# ATMEGA-BOARD.net
KiCad netlist of a schematic drawn in Altium Designer
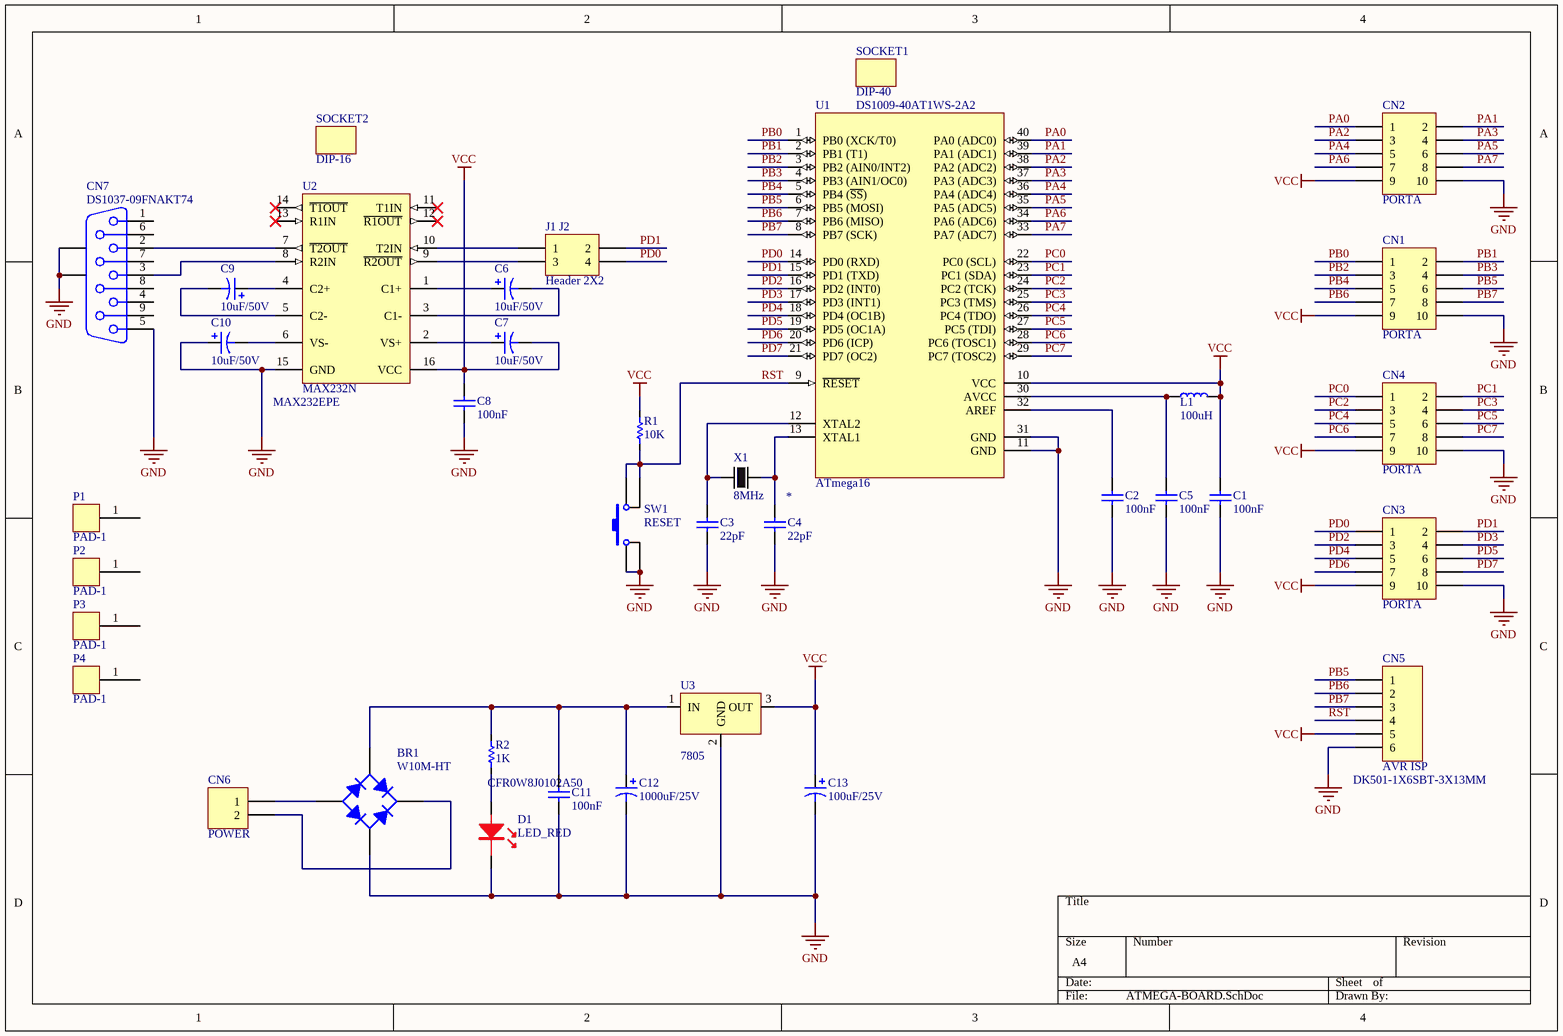
[diagram p0: ATMEGA-BOARD.SchDoc]

(export (version "E")
  (design (tool "Eeschema 10.0.6"))
  (components
    (comp (ref "BR1")
      (value "W10M-HT")
      (footprint "DIODE-WOB")
      (description "Full Wave Diode Bridge")
      (libsource (lib "Miscellaneous Devices") (part "Bridge1"))
    )
    (comp (ref "C1")
      (value "100nF")
      (footprint "CAP0.2N")
      (description "Capacitor")
      (libsource (lib "Miscellaneous Devices") (part "Cap"))
    )
    (comp (ref "C2")
      (value "100nF")
      (footprint "CAP0.2N")
      (description "Capacitor")
      (libsource (lib "Miscellaneous Devices") (part "Cap"))
    )
    (comp (ref "C3")
      (value "22pF")
      (footprint "CAP0.2N")
      (description "Capacitor")
      (libsource (lib "Miscellaneous Devices") (part "Cap"))
    )
    (comp (ref "C4")
      (value "22pF")
      (footprint "CAP0.2N")
      (description "Capacitor")
      (libsource (lib "Miscellaneous Devices") (part "Cap"))
    )
    (comp (ref "C5")
      (value "100nF")
      (footprint "CAP0.2N")
      (description "Capacitor")
      (libsource (lib "Miscellaneous Devices") (part "Cap"))
    )
    (comp (ref "C6")
      (value "10uF/50V")
      (footprint "CAP_ALUM_5x11x2.5_V")
      (description "Polarized Capacitor")
      (libsource (lib "Miscellaneous Devices") (part "Cap Pol3"))
    )
    (comp (ref "C7")
      (value "10uF/50V")
      (footprint "CAP_ALUM_5x11x2.5_V")
      (description "Polarized Capacitor")
      (libsource (lib "Miscellaneous Devices") (part "Cap Pol3"))
    )
    (comp (ref "C8")
      (value "100nF")
      (footprint "CAP0.2N")
      (description "Capacitor")
      (libsource (lib "Miscellaneous Devices") (part "Cap"))
    )
    (comp (ref "C9")
      (value "10uF/50V")
      (footprint "CAP_ALUM_5x11x2.5_V")
      (description "Polarized Capacitor")
      (libsource (lib "Miscellaneous Devices") (part "Cap Pol3"))
    )
    (comp (ref "C10")
      (value "10uF/50V")
      (footprint "CAP_ALUM_5x11x2.5_V")
      (description "Polarized Capacitor")
      (libsource (lib "Miscellaneous Devices") (part "Cap Pol3"))
    )
    (comp (ref "C11")
      (value "100nF")
      (footprint "CAP0.2N")
      (description "Capacitor")
      (libsource (lib "Miscellaneous Devices") (part "Cap"))
    )
    (comp (ref "C12")
      (value "1000uF/25V")
      (footprint "CAP_ALUM_10x17x5_V")
      (description "Polarized Capacitor")
      (libsource (lib "Miscellaneous Devices") (part "Cap Pol3"))
    )
    (comp (ref "C13")
      (value "100uF/25V")
      (footprint "CAP_ALUM_6.3x11.2x2.5_V")
      (description "Polarized Capacitor")
      (libsource (lib "Miscellaneous Devices") (part "Cap Pol3"))
    )
    (comp (ref "CN1")
      (value "PORTA")
      (footprint "CON-DS1013-10SSIB1")
      (description "Header, 5-Pin, Dual row, Right Angle")
      (libsource (lib "Miscellaneous Connectors") (part "Header 5X2H"))
    )
    (comp (ref "CN2")
      (value "PORTA")
      (footprint "CON-DS1013-10SSIB1")
      (description "Header, 5-Pin, Dual row, Right Angle")
      (libsource (lib "Miscellaneous Connectors") (part "Header 5X2H"))
    )
    (comp (ref "CN3")
      (value "PORTA")
      (footprint "CON-DS1013-10SSIB1")
      (description "Header, 5-Pin, Dual row, Right Angle")
      (libsource (lib "Miscellaneous Connectors") (part "Header 5X2H"))
    )
    (comp (ref "CN4")
      (value "PORTA")
      (footprint "CON-DS1013-10SSIB1")
      (description "Header, 5-Pin, Dual row, Right Angle")
      (libsource (lib "Miscellaneous Connectors") (part "Header 5X2H"))
    )
    (comp (ref "CN5")
      (value "AVR ISP")
      (footprint "Pin Header S/M 06x1 TH Pitch 2.54mm")
      (description "Header, 6-Pin")
      (fields (field (name "OZDISAN KODU") "DK501-1X6SBT-3X13MM"))
      (libsource (lib "Miscellaneous Connectors") (part "Header 6"))
    )
    (comp (ref "CN6")
      (value "POWER")
      (footprint "Klemens-DG126-5.0-02P-14-00AH")
      (description "Header, 2-Pin")
      (libsource (lib "Miscellaneous Connectors") (part "Header 2"))
    )
    (comp (ref "CN7")
      (value "DS1037-09FNAKT74")
      (footprint "CON-DB9FLW")
      (description "CONNECTOR DSUB 9PIN 90C PCB TYPE FEMALE")
      (libsource (lib "Miscellaneous Connectors") (part "D Connector 9"))
    )
    (comp (ref "D1") (value "LED_RED") (footprint "LED3M-RED") (libsource (lib "ali_lib") (part "LED_RED")))
    (comp (ref "J1 J2")
      (value "Header 2X2")
      (footprint "Pin Header S/M 02x2 TH Pitch 2.54mm")
      (description "Header, 2-Pin, Dual row")
      (libsource (lib "Miscellaneous Connectors") (part "Header 2X2"))
    )
    (comp (ref "L1")
      (value "100uH")
      (footprint "IND-AL0412")
      (description "Inductor")
      (libsource (lib "ali_lib") (part "Inductor"))
    )
    (comp (ref "P1") (value "PAD-1") (footprint "DOUBLE-3") (libsource (lib "ali_lib") (part "PAD-1")))
    (comp (ref "P2") (value "PAD-1") (footprint "DOUBLE-3") (libsource (lib "ali_lib") (part "PAD-1")))
    (comp (ref "P3") (value "PAD-1") (footprint "DOUBLE-3") (libsource (lib "ali_lib") (part "PAD-1")))
    (comp (ref "P4") (value "PAD-1") (footprint "DOUBLE-3") (libsource (lib "ali_lib") (part "PAD-1")))
    (comp (ref "R1")
      (value "10K")
      (footprint "RES_AXIAL-0.3")
      (description "Resistor")
      (libsource (lib "ali_lib") (part "R"))
    )
    (comp (ref "R2")
      (value "1K")
      (footprint "RES_AXIAL-0.3")
      (description "Resistor")
      (fields (field (name "OZDISAN KODU") "CFR0W8J0102A50"))
      (libsource (lib "ali_lib") (part "R"))
    )
    (comp (ref "SOCKET1")
      (value "DIP-40")
      (fields (field (name "OZDISAN KODU") "DS1009-40AT1WS-2A2"))
      (libsource (lib "ali_lib") (part "MECHANIC"))
    )
    (comp (ref "SOCKET2") (value "DIP-16") (libsource (lib "ali_lib") (part "MECHANIC")))
    (comp (ref "SW1")
      (value "RESET")
      (footprint "Switch-6x6x4.3")
      (description "Switch")
      (libsource (lib "ali_lib") (part "SW-PB"))
    )
    (comp (ref "U1")
      (value "ATmega16")
      (footprint "DIP40N")
      (description "8-bit AVR Microcontroller, 4.5-5.5V")
      (fields (field (name "OZDISAN KODU") "*"))
      (libsource (lib "ali_lib") (part "MC-8B-ATM32-IL40"))
    )
    (comp (ref "U2")
      (value "MAX232N")
      (footprint "DIP16N")
      (description "Dual EIA-232 Driver / Receiver, 0 to 70 degC, 16-Pin PDIP (N), Pb-Free (RoHS)")
      (fields (field (name "OZDISAN KODU") "MAX232EPE"))
      (libsource (lib "ali_lib") (part "TI-MAX232-PDIP_N-16"))
    )
    (comp (ref "U3")
      (value "7805")
      (footprint "TO-220_3-H")
      (description "IC REG LINEAR 5V 500MA DPAK")
      (libsource (lib "ali_lib") (part "78M05"))
    )
    (comp (ref "X1")
      (value "8MHz")
      (footprint "XTAL_DIP")
      (description "XTAL")
      (libsource (lib "ali_lib") (part "XTAL"))
    )
  )
  (nets
    (net (code "1") (name "/PA0") (class "Default")
      (node (ref "CN2") (pin "1") (pinfunction "1_1") (pintype "passive"))
      (node (ref "U1") (pin "40") (pinfunction "PA0_(ADC0)_40") (pintype "bidirectional"))
    )
    (net (code "2") (name "/PA1") (class "Default")
      (node (ref "CN2") (pin "2") (pinfunction "2_2") (pintype "passive"))
      (node (ref "U1") (pin "39") (pinfunction "PA1_(ADC1)_39") (pintype "bidirectional"))
    )
    (net (code "3") (name "/PA2") (class "Default")
      (node (ref "CN2") (pin "3") (pinfunction "3_3") (pintype "passive"))
      (node (ref "U1") (pin "38") (pinfunction "PA2_(ADC2)_38") (pintype "bidirectional"))
    )
    (net (code "4") (name "/PA3") (class "Default")
      (node (ref "CN2") (pin "4") (pinfunction "4_4") (pintype "passive"))
      (node (ref "U1") (pin "37") (pinfunction "PA3_(ADC3)_37") (pintype "bidirectional"))
    )
    (net (code "5") (name "/PA4") (class "Default")
      (node (ref "CN2") (pin "5") (pinfunction "5_5") (pintype "passive"))
      (node (ref "U1") (pin "36") (pinfunction "PA4_(ADC4)_36") (pintype "bidirectional"))
    )
    (net (code "6") (name "/PA5") (class "Default")
      (node (ref "CN2") (pin "6") (pinfunction "6_6") (pintype "passive"))
      (node (ref "U1") (pin "35") (pinfunction "PA5_(ADC5)_35") (pintype "bidirectional"))
    )
    (net (code "7") (name "/PA6") (class "Default")
      (node (ref "CN2") (pin "7") (pinfunction "7_7") (pintype "passive"))
      (node (ref "U1") (pin "34") (pinfunction "PA6_(ADC6)_34") (pintype "bidirectional"))
    )
    (net (code "8") (name "/PA7") (class "Default")
      (node (ref "CN2") (pin "8") (pinfunction "8_8") (pintype "passive"))
      (node (ref "U1") (pin "33") (pinfunction "PA7_(ADC7)_33") (pintype "bidirectional"))
    )
    (net (code "9") (name "/PB0") (class "Default")
      (node (ref "CN1") (pin "1") (pinfunction "1_1") (pintype "passive"))
      (node (ref "U1") (pin "1") (pinfunction "PB0_(XCK/T0)_1") (pintype "bidirectional"))
    )
    (net (code "10") (name "/PB1") (class "Default")
      (node (ref "CN1") (pin "2") (pinfunction "2_2") (pintype "passive"))
      (node (ref "U1") (pin "2") (pinfunction "PB1_(T1)_2") (pintype "bidirectional"))
    )
    (net (code "11") (name "/PB2") (class "Default")
      (node (ref "CN1") (pin "3") (pinfunction "3_3") (pintype "passive"))
      (node (ref "U1") (pin "3") (pinfunction "PB2_(AIN0/INT2)_3") (pintype "bidirectional"))
    )
    (net (code "12") (name "/PB3") (class "Default")
      (node (ref "CN1") (pin "4") (pinfunction "4_4") (pintype "passive"))
      (node (ref "U1") (pin "4") (pinfunction "PB3_(AIN1/OC0)_4") (pintype "bidirectional"))
    )
    (net (code "13") (name "/PB4") (class "Default")
      (node (ref "CN1") (pin "5") (pinfunction "5_5") (pintype "passive"))
      (node (ref "U1") (pin "5") (pinfunction "PB4_(~{SS})_5") (pintype "bidirectional"))
    )
    (net (code "14") (name "/PB5") (class "Default")
      (node (ref "CN1") (pin "6") (pinfunction "6_6") (pintype "passive"))
      (node (ref "CN5") (pin "1") (pinfunction "1_1") (pintype "passive"))
      (node (ref "U1") (pin "6") (pinfunction "PB5_(MOSI)_6") (pintype "bidirectional"))
    )
    (net (code "15") (name "/PB6") (class "Default")
      (node (ref "CN1") (pin "7") (pinfunction "7_7") (pintype "passive"))
      (node (ref "CN5") (pin "2") (pinfunction "2_2") (pintype "passive"))
      (node (ref "U1") (pin "7") (pinfunction "PB6_(MISO)_7") (pintype "bidirectional"))
    )
    (net (code "16") (name "/PB7") (class "Default")
      (node (ref "CN1") (pin "8") (pinfunction "8_8") (pintype "passive"))
      (node (ref "CN5") (pin "3") (pinfunction "3_3") (pintype "passive"))
      (node (ref "U1") (pin "8") (pinfunction "PB7_(SCK)_8") (pintype "bidirectional"))
    )
    (net (code "17") (name "/PC0") (class "Default")
      (node (ref "CN4") (pin "1") (pinfunction "1_1") (pintype "passive"))
      (node (ref "U1") (pin "22") (pinfunction "PC0_(SCL)_22") (pintype "bidirectional"))
    )
    (net (code "18") (name "/PC1") (class "Default")
      (node (ref "CN4") (pin "2") (pinfunction "2_2") (pintype "passive"))
      (node (ref "U1") (pin "23") (pinfunction "PC1_(SDA)_23") (pintype "bidirectional"))
    )
    (net (code "19") (name "/PC2") (class "Default")
      (node (ref "CN4") (pin "3") (pinfunction "3_3") (pintype "passive"))
      (node (ref "U1") (pin "24") (pinfunction "PC2_(TCK)_24") (pintype "bidirectional"))
    )
    (net (code "20") (name "/PC3") (class "Default")
      (node (ref "CN4") (pin "4") (pinfunction "4_4") (pintype "passive"))
      (node (ref "U1") (pin "25") (pinfunction "PC3_(TMS)_25") (pintype "bidirectional"))
    )
    (net (code "21") (name "/PC4") (class "Default")
      (node (ref "CN4") (pin "5") (pinfunction "5_5") (pintype "passive"))
      (node (ref "U1") (pin "26") (pinfunction "PC4_(TDO)_26") (pintype "bidirectional"))
    )
    (net (code "22") (name "/PC5") (class "Default")
      (node (ref "CN4") (pin "6") (pinfunction "6_6") (pintype "passive"))
      (node (ref "U1") (pin "27") (pinfunction "PC5_(TDI)_27") (pintype "bidirectional"))
    )
    (net (code "23") (name "/PC6") (class "Default")
      (node (ref "CN4") (pin "7") (pinfunction "7_7") (pintype "passive"))
      (node (ref "U1") (pin "28") (pinfunction "PC6_(TOSC1)_28") (pintype "bidirectional"))
    )
    (net (code "24") (name "/PC7") (class "Default")
      (node (ref "CN4") (pin "8") (pinfunction "8_8") (pintype "passive"))
      (node (ref "U1") (pin "29") (pinfunction "PC7_(TOSC2)_29") (pintype "bidirectional"))
    )
    (net (code "25") (name "/PD0") (class "Default")
      (node (ref "CN3") (pin "1") (pinfunction "1_1") (pintype "passive"))
      (node (ref "J1 J2") (pin "4") (pinfunction "4_4") (pintype "passive"))
      (node (ref "U1") (pin "14") (pinfunction "PD0_(RXD)_14") (pintype "bidirectional"))
    )
    (net (code "26") (name "/PD1") (class "Default")
      (node (ref "CN3") (pin "2") (pinfunction "2_2") (pintype "passive"))
      (node (ref "J1 J2") (pin "2") (pinfunction "2_2") (pintype "passive"))
      (node (ref "U1") (pin "15") (pinfunction "PD1_(TXD)_15") (pintype "bidirectional"))
    )
    (net (code "27") (name "/PD2") (class "Default")
      (node (ref "CN3") (pin "3") (pinfunction "3_3") (pintype "passive"))
      (node (ref "U1") (pin "16") (pinfunction "PD2_(INT0)_16") (pintype "bidirectional"))
    )
    (net (code "28") (name "/PD3") (class "Default")
      (node (ref "CN3") (pin "4") (pinfunction "4_4") (pintype "passive"))
      (node (ref "U1") (pin "17") (pinfunction "PD3_(INT1)_17") (pintype "bidirectional"))
    )
    (net (code "29") (name "/PD4") (class "Default")
      (node (ref "CN3") (pin "5") (pinfunction "5_5") (pintype "passive"))
      (node (ref "U1") (pin "18") (pinfunction "PD4_(OC1B)_18") (pintype "bidirectional"))
    )
    (net (code "30") (name "/PD5") (class "Default")
      (node (ref "CN3") (pin "6") (pinfunction "6_6") (pintype "passive"))
      (node (ref "U1") (pin "19") (pinfunction "PD5_(OC1A)_19") (pintype "bidirectional"))
    )
    (net (code "31") (name "/PD6") (class "Default")
      (node (ref "CN3") (pin "7") (pinfunction "7_7") (pintype "passive"))
      (node (ref "U1") (pin "20") (pinfunction "PD6_(ICP)_20") (pintype "bidirectional"))
    )
    (net (code "32") (name "/PD7") (class "Default")
      (node (ref "CN3") (pin "8") (pinfunction "8_8") (pintype "passive"))
      (node (ref "U1") (pin "21") (pinfunction "PD7_(OC2)_21") (pintype "bidirectional"))
    )
    (net (code "33") (name "/RST") (class "Default")
      (node (ref "CN5") (pin "4") (pinfunction "4_4") (pintype "passive"))
      (node (ref "R1") (pin "1") (pinfunction "1_1") (pintype "passive"))
      (node (ref "SW1") (pin "2") (pinfunction "2_2") (pintype "passive"))
      (node (ref "U1") (pin "9") (pinfunction "~{RESET}_9") (pintype "input"))
    )
    (net (code "34") (name "GND") (class "Default")
      (node (ref "BR1") (pin "2") (pinfunction "C_2") (pintype "passive"))
      (node (ref "C1") (pin "1") (pinfunction "1_1") (pintype "passive"))
      (node (ref "C10") (pin "1") (pinfunction "1_1") (pintype "passive"))
      (node (ref "C11") (pin "1") (pinfunction "1_1") (pintype "passive"))
      (node (ref "C12") (pin "2") (pinfunction "2_2") (pintype "passive"))
      (node (ref "C13") (pin "2") (pinfunction "2_2") (pintype "passive"))
      (node (ref "C2") (pin "1") (pinfunction "1_1") (pintype "passive"))
      (node (ref "C3") (pin "1") (pinfunction "1_1") (pintype "passive"))
      (node (ref "C4") (pin "1") (pinfunction "1_1") (pintype "passive"))
      (node (ref "C5") (pin "1") (pinfunction "1_1") (pintype "passive"))
      (node (ref "C8") (pin "1") (pinfunction "1_1") (pintype "passive"))
      (node (ref "CN1") (pin "10") (pinfunction "10_10") (pintype "passive"))
      (node (ref "CN2") (pin "10") (pinfunction "10_10") (pintype "passive"))
      (node (ref "CN3") (pin "10") (pinfunction "10_10") (pintype "passive"))
      (node (ref "CN4") (pin "10") (pinfunction "10_10") (pintype "passive"))
      (node (ref "CN5") (pin "6") (pinfunction "6_6") (pintype "passive"))
      (node (ref "CN7") (pin "5") (pinfunction "5_5") (pintype "passive"))
      (node (ref "CN7") (pin "BO1") (pinfunction "MH2_BO1") (pintype "passive"))
      (node (ref "CN7") (pin "BO2") (pinfunction "MH1_BO2") (pintype "passive"))
      (node (ref "D1") (pin "2") (pinfunction "K_2") (pintype "passive"))
      (node (ref "SW1") (pin "1") (pinfunction "1_1") (pintype "passive"))
      (node (ref "U1") (pin "11") (pinfunction "GND_11") (pintype "power_in"))
      (node (ref "U1") (pin "31") (pinfunction "GND_31") (pintype "power_in"))
      (node (ref "U2") (pin "15") (pinfunction "GND_15") (pintype "power_in"))
      (node (ref "U3") (pin "2") (pinfunction "GND_2") (pintype "passive"))
    )
    (net (code "35") (name "Net-(BR1-A)") (class "Default")
      (node (ref "BR1") (pin "3") (pinfunction "A_3") (pintype "passive"))
      (node (ref "CN6") (pin "1") (pinfunction "1_1") (pintype "passive"))
    )
    (net (code "36") (name "Net-(BR1-K)") (class "Default")
      (node (ref "BR1") (pin "1") (pinfunction "K_1") (pintype "passive"))
      (node (ref "CN6") (pin "2") (pinfunction "2_2") (pintype "passive"))
    )
    (net (code "37") (name "Net-(D1-A)") (class "Default")
      (node (ref "D1") (pin "1") (pinfunction "A_1") (pintype "passive"))
      (node (ref "R2") (pin "1") (pinfunction "1_1") (pintype "passive"))
    )
    (net (code "38") (name "Net-(U1-AREF)") (class "Default")
      (node (ref "C2") (pin "2") (pinfunction "2_2") (pintype "passive"))
      (node (ref "U1") (pin "32") (pinfunction "AREF_32") (pintype "passive"))
    )
    (net (code "39") (name "Net-(U1-AVCC)") (class "Default")
      (node (ref "C5") (pin "2") (pinfunction "2_2") (pintype "passive"))
      (node (ref "L1") (pin "1") (pinfunction "1_1") (pintype "passive"))
      (node (ref "U1") (pin "30") (pinfunction "AVCC_30") (pintype "power_in"))
    )
    (net (code "40") (name "Net-(U1-XTAL1)") (class "Default")
      (node (ref "C4") (pin "2") (pinfunction "2_2") (pintype "passive"))
      (node (ref "U1") (pin "13") (pinfunction "XTAL1_13") (pintype "passive"))
      (node (ref "X1") (pin "1") (pinfunction "1_1") (pintype "passive"))
    )
    (net (code "41") (name "Net-(U1-XTAL2)") (class "Default")
      (node (ref "C3") (pin "2") (pinfunction "2_2") (pintype "passive"))
      (node (ref "U1") (pin "12") (pinfunction "XTAL2_12") (pintype "passive"))
      (node (ref "X1") (pin "2") (pinfunction "2_2") (pintype "passive"))
    )
    (net (code "42") (name "Net-(U2-C1+)") (class "Default")
      (node (ref "C6") (pin "1") (pinfunction "1_1") (pintype "passive"))
      (node (ref "U2") (pin "1") (pinfunction "C1+_1") (pintype "passive"))
    )
    (net (code "43") (name "Net-(U2-C1-)") (class "Default")
      (node (ref "C6") (pin "2") (pinfunction "2_2") (pintype "passive"))
      (node (ref "U2") (pin "3") (pinfunction "C1-_3") (pintype "passive"))
    )
    (net (code "44") (name "Net-(U2-C2+)") (class "Default")
      (node (ref "C9") (pin "1") (pinfunction "1_1") (pintype "passive"))
      (node (ref "U2") (pin "4") (pinfunction "C2+_4") (pintype "passive"))
    )
    (net (code "45") (name "Net-(U2-C2-)") (class "Default")
      (node (ref "C9") (pin "2") (pinfunction "2_2") (pintype "passive"))
      (node (ref "U2") (pin "5") (pinfunction "C2-_5") (pintype "passive"))
    )
    (net (code "46") (name "Net-(U2-R2IN)") (class "Default")
      (node (ref "CN7") (pin "3") (pinfunction "3_3") (pintype "passive"))
      (node (ref "U2") (pin "8") (pinfunction "R2IN_8") (pintype "input"))
    )
    (net (code "47") (name "Net-(U2-T2IN)") (class "Default")
      (node (ref "J1 J2") (pin "1") (pinfunction "1_1") (pintype "passive"))
      (node (ref "U2") (pin "10") (pinfunction "T2IN_10") (pintype "input"))
    )
    (net (code "48") (name "Net-(U2-VS+)") (class "Default")
      (node (ref "C7") (pin "1") (pinfunction "1_1") (pintype "passive"))
      (node (ref "U2") (pin "2") (pinfunction "VS+_2") (pintype "power_in"))
    )
    (net (code "49") (name "Net-(U2-VS-)") (class "Default")
      (node (ref "C10") (pin "2") (pinfunction "2_2") (pintype "passive"))
      (node (ref "U2") (pin "6") (pinfunction "VS-_6") (pintype "power_in"))
    )
    (net (code "50") (name "Net-(U2-~{R2OUT})") (class "Default")
      (node (ref "J1 J2") (pin "3") (pinfunction "3_3") (pintype "passive"))
      (node (ref "U2") (pin "9") (pinfunction "~{R2OUT}_9") (pintype "output"))
    )
    (net (code "51") (name "Net-(U2-~{T2OUT})") (class "Default")
      (node (ref "CN7") (pin "2") (pinfunction "2_2") (pintype "passive"))
      (node (ref "U2") (pin "7") (pinfunction "~{T2OUT}_7") (pintype "output"))
    )
    (net (code "52") (name "Net-(U3-IN)") (class "Default")
      (node (ref "BR1") (pin "4") (pinfunction "C_4") (pintype "passive"))
      (node (ref "C11") (pin "2") (pinfunction "2_2") (pintype "passive"))
      (node (ref "C12") (pin "1") (pinfunction "1_1") (pintype "passive"))
      (node (ref "R2") (pin "2") (pinfunction "2_2") (pintype "passive"))
      (node (ref "U3") (pin "1") (pinfunction "IN_1") (pintype "passive"))
    )
    (net (code "53") (name "VCC") (class "Default")
      (node (ref "C1") (pin "2") (pinfunction "2_2") (pintype "passive"))
      (node (ref "C13") (pin "1") (pinfunction "1_1") (pintype "passive"))
      (node (ref "C7") (pin "2") (pinfunction "2_2") (pintype "passive"))
      (node (ref "C8") (pin "2") (pinfunction "2_2") (pintype "passive"))
      (node (ref "CN1") (pin "9") (pinfunction "9_9") (pintype "passive"))
      (node (ref "CN2") (pin "9") (pinfunction "9_9") (pintype "passive"))
      (node (ref "CN3") (pin "9") (pinfunction "9_9") (pintype "passive"))
      (node (ref "CN4") (pin "9") (pinfunction "9_9") (pintype "passive"))
      (node (ref "CN5") (pin "5") (pinfunction "5_5") (pintype "passive"))
      (node (ref "L1") (pin "2") (pinfunction "2_2") (pintype "passive"))
      (node (ref "R1") (pin "2") (pinfunction "2_2") (pintype "passive"))
      (node (ref "U1") (pin "10") (pinfunction "VCC_10") (pintype "power_in"))
      (node (ref "U2") (pin "16") (pinfunction "VCC_16") (pintype "power_in"))
      (node (ref "U3") (pin "3") (pinfunction "OUT_3") (pintype "passive"))
    )
    (net (code "54") (name "unconnected-(CN7-Pad1)") (class "Default")
      (node (ref "CN7") (pin "1") (pinfunction "1_1") (pintype "passive"))
    )
    (net (code "55") (name "unconnected-(CN7-Pad4)") (class "Default")
      (node (ref "CN7") (pin "4") (pinfunction "4_4") (pintype "passive"))
    )
    (net (code "56") (name "unconnected-(CN7-Pad6)") (class "Default")
      (node (ref "CN7") (pin "6") (pinfunction "6_6") (pintype "passive"))
    )
    (net (code "57") (name "unconnected-(CN7-Pad7)") (class "Default")
      (node (ref "CN7") (pin "7") (pinfunction "7_7") (pintype "passive"))
    )
    (net (code "58") (name "unconnected-(CN7-Pad8)") (class "Default")
      (node (ref "CN7") (pin "8") (pinfunction "8_8") (pintype "passive"))
    )
    (net (code "59") (name "unconnected-(CN7-Pad9)") (class "Default")
      (node (ref "CN7") (pin "9") (pinfunction "9_9") (pintype "passive"))
    )
    (net (code "60") (name "unconnected-(P1-Pad1)") (class "Default")
      (node (ref "P1") (pin "1") (pintype "passive"))
    )
    (net (code "61") (name "unconnected-(P2-Pad1)") (class "Default")
      (node (ref "P2") (pin "1") (pintype "passive"))
    )
    (net (code "62") (name "unconnected-(P3-Pad1)") (class "Default")
      (node (ref "P3") (pin "1") (pintype "passive"))
    )
    (net (code "63") (name "unconnected-(P4-Pad1)") (class "Default")
      (node (ref "P4") (pin "1") (pintype "passive"))
    )
    (net (code "64") (name "unconnected-(U2-R1IN-Pad13)") (class "Default")
      (node (ref "U2") (pin "13") (pinfunction "R1IN_13") (pintype "input+no_connect"))
    )
    (net (code "65") (name "unconnected-(U2-T1IN-Pad11)") (class "Default")
      (node (ref "U2") (pin "11") (pinfunction "T1IN_11") (pintype "input+no_connect"))
    )
    (net (code "66") (name "unconnected-(U2-~{R1OUT}-Pad12)") (class "Default")
      (node (ref "U2") (pin "12") (pinfunction "~{R1OUT}_12") (pintype "output+no_connect"))
    )
    (net (code "67") (name "unconnected-(U2-~{T1OUT}-Pad14)") (class "Default")
      (node (ref "U2") (pin "14") (pinfunction "~{T1OUT}_14") (pintype "output+no_connect"))
    )
  )
)
